# CH340G.net
KiCad netlist of a schematic drawn in Altium Designer
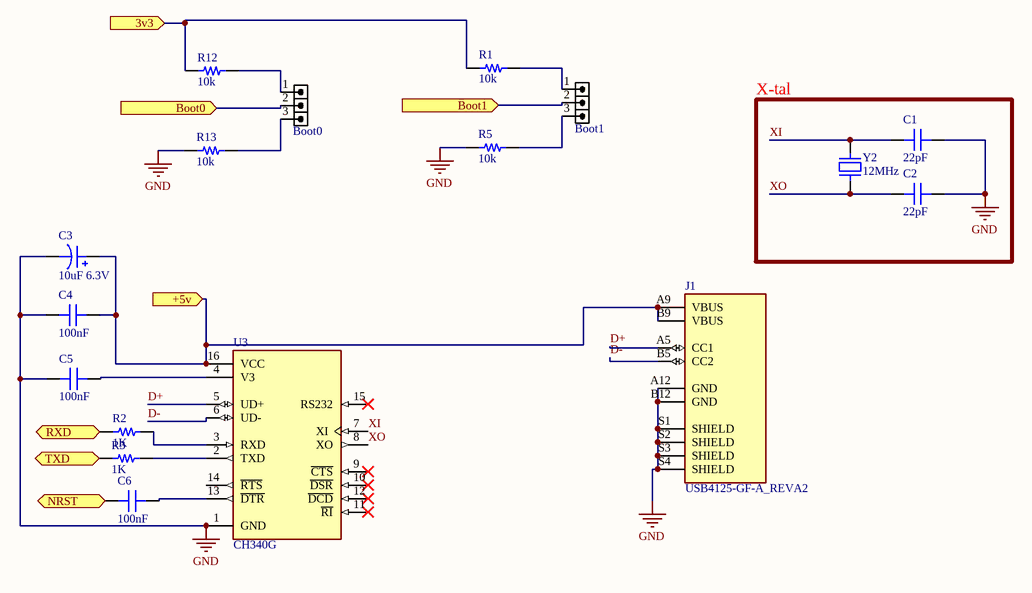
[diagram p0: CH340G.SchDoc]

(export (version "E")
  (design (tool "Eeschema 10.0.6"))
  (components
    (comp (ref "Boot0")
      (value "HDRM3")
      (footprint "HDR_1X3")
      (description "CONN, HEADER, Male, pitch: 2.54mm, 3POS")
      (libsource (lib "Conn Header") (part "HDR_1X3"))
    )
    (comp (ref "Boot1")
      (value "HDRM3")
      (footprint "HDR_1X3")
      (description "CONN, HEADER, Male, pitch: 2.54mm, 3POS")
      (libsource (lib "Conn Header") (part "HDR_1X3"))
    )
    (comp (ref "C1")
      (value "22pF")
      (footprint "CAP 0805_2012")
      (description "SMT Capacitor")
      (libsource (lib "Capacitor") (part "Cap 0805"))
    )
    (comp (ref "C2")
      (value "22pF")
      (footprint "CAP 0805_2012")
      (description "SMT Capacitor")
      (libsource (lib "Capacitor") (part "Cap 0805"))
    )
    (comp (ref "C3")
      (value "10uF 6.3V")
      (footprint "CAP ALTH D8 L3.5 H12.5")
      (description "TH Aluminum Polymer Capacitor")
      (libsource (lib "Capacitor") (part "Cap Alu TH D8mm L3.5mm H12.5mm"))
    )
    (comp (ref "C4")
      (value "100nF")
      (footprint "CAP 0805_2012")
      (description "SMT Capacitor")
      (libsource (lib "Capacitor") (part "Cap 0805"))
    )
    (comp (ref "C5")
      (value "100nF")
      (footprint "CAP 0805_2012")
      (description "SMT Capacitor")
      (libsource (lib "Capacitor") (part "Cap 0805"))
    )
    (comp (ref "C6")
      (value "100nF")
      (footprint "CAP 0805_2012")
      (description "SMT Capacitor")
      (libsource (lib "Capacitor") (part "Cap 0805"))
    )
    (comp (ref "J1")
      (value "USB4125-GF-A_REVA2")
      (footprint "GCT_USB4125-GF-A_REVA2")
      (libsource (lib "Type-C 6pin") (part "USB4125-GF-A_REVA2"))
    )
    (comp (ref "R1")
      (value "10k")
      (footprint "RES 0805_2012")
      (description "SMT Resistor")
      (libsource (lib "Resistor") (part "Res 0805"))
    )
    (comp (ref "R2")
      (value "1K")
      (footprint "RES 0805_2012")
      (description "SMT Resistor")
      (libsource (lib "Resistor") (part "Res 0805"))
    )
    (comp (ref "R3")
      (value "1K")
      (footprint "RES 0805_2012")
      (description "SMT Resistor")
      (libsource (lib "Resistor") (part "Res 0805"))
    )
    (comp (ref "R5")
      (value "10k")
      (footprint "RES 0805_2012")
      (description "SMT Resistor")
      (libsource (lib "Resistor") (part "Res 0805"))
    )
    (comp (ref "R12")
      (value "10k")
      (footprint "RES 0805_2012")
      (description "SMT Resistor")
      (libsource (lib "Resistor") (part "Res 0805"))
    )
    (comp (ref "R13")
      (value "10k")
      (footprint "RES 0805_2012")
      (description "SMT Resistor")
      (libsource (lib "Resistor") (part "Res 0805"))
    )
    (comp (ref "U3")
      (value "CH340G")
      (footprint "SOIC127P600X180-16N")
      (description "USB Interface Integrated Circuit")
      (fields (field (name "MP") "Ch340G") (field (name "MF") "WCH"))
      (libsource (lib "CH340G") (part "CH340G"))
    )
    (comp (ref "Y2")
      (value "12MHz")
      (footprint "HC-49S SMD")
      (description "SMT Crystal")
      (fields (field (name "PARTNUMBER") "ABLS-8.000MHZ-K4T"))
      (libsource (lib "Xtal") (part "Crystal HC-49S SMD 8MHz"))
    )
  )
  (nets
    (net (code "1") (name "/+5v") (class "Default")
      (node (ref "C3") (pin "1") (pinfunction "1_1") (pintype "passive"))
      (node (ref "C4") (pin "1") (pinfunction "1_1") (pintype "passive"))
      (node (ref "J1") (pin "A9") (pinfunction "VBUS_A9") (pintype "power_in"))
      (node (ref "J1") (pin "B9") (pinfunction "VBUS_B9") (pintype "power_in"))
      (node (ref "U3") (pin "16") (pinfunction "VCC_16") (pintype "power_in"))
    )
    (net (code "2") (name "/3v3") (class "Default")
      (node (ref "R1") (pin "1") (pinfunction "1_1") (pintype "passive"))
      (node (ref "R12") (pin "1") (pinfunction "1_1") (pintype "passive"))
    )
    (net (code "3") (name "/Boot0") (class "Default")
      (node (ref "Boot0") (pin "2") (pinfunction "2_2") (pintype "passive"))
    )
    (net (code "4") (name "/Boot1") (class "Default")
      (node (ref "Boot1") (pin "2") (pinfunction "2_2") (pintype "passive"))
    )
    (net (code "5") (name "/D+") (class "Default")
      (node (ref "J1") (pin "A5") (pinfunction "CC1_A5") (pintype "bidirectional"))
      (node (ref "U3") (pin "5") (pinfunction "UD+_5") (pintype "bidirectional"))
    )
    (net (code "6") (name "/D-") (class "Default")
      (node (ref "J1") (pin "B5") (pinfunction "CC2_B5") (pintype "bidirectional"))
      (node (ref "U3") (pin "6") (pinfunction "UD-_6") (pintype "bidirectional"))
    )
    (net (code "7") (name "/NRST") (class "Default")
      (node (ref "C6") (pin "1") (pinfunction "1_1") (pintype "passive"))
    )
    (net (code "8") (name "/RXD") (class "Default")
      (node (ref "R2") (pin "1") (pinfunction "1_1") (pintype "passive"))
    )
    (net (code "9") (name "/TXD") (class "Default")
      (node (ref "R3") (pin "1") (pinfunction "1_1") (pintype "passive"))
    )
    (net (code "10") (name "/XI") (class "Default")
      (node (ref "C1") (pin "1") (pinfunction "1_1") (pintype "passive"))
      (node (ref "U3") (pin "7") (pinfunction "XI_7") (pintype "input"))
      (node (ref "Y2") (pin "2") (pinfunction "2_2") (pintype "passive"))
    )
    (net (code "11") (name "/XO") (class "Default")
      (node (ref "C2") (pin "1") (pinfunction "1_1") (pintype "passive"))
      (node (ref "U3") (pin "8") (pinfunction "XO_8") (pintype "output"))
      (node (ref "Y2") (pin "1") (pinfunction "1_1") (pintype "passive"))
    )
    (net (code "12") (name "GND") (class "Default")
      (node (ref "C1") (pin "2") (pinfunction "2_2") (pintype "passive"))
      (node (ref "C2") (pin "2") (pinfunction "2_2") (pintype "passive"))
      (node (ref "C3") (pin "2") (pinfunction "2_2") (pintype "passive"))
      (node (ref "C4") (pin "2") (pinfunction "2_2") (pintype "passive"))
      (node (ref "C5") (pin "1") (pinfunction "1_1") (pintype "passive"))
      (node (ref "J1") (pin "A12") (pinfunction "GND_A12") (pintype "power_in"))
      (node (ref "J1") (pin "B12") (pinfunction "GND_B12") (pintype "power_in"))
      (node (ref "J1") (pin "S1") (pinfunction "SHIELD_S1") (pintype "passive"))
      (node (ref "J1") (pin "S2") (pinfunction "SHIELD_S2") (pintype "passive"))
      (node (ref "J1") (pin "S3") (pinfunction "SHIELD_S3") (pintype "passive"))
      (node (ref "J1") (pin "S4") (pinfunction "SHIELD_S4") (pintype "passive"))
      (node (ref "R13") (pin "1") (pinfunction "1_1") (pintype "passive"))
      (node (ref "R5") (pin "1") (pinfunction "1_1") (pintype "passive"))
      (node (ref "U3") (pin "1") (pinfunction "GND_1") (pintype "power_in"))
    )
    (net (code "13") (name "Net-(Boot0-Pad1)") (class "Default")
      (node (ref "Boot0") (pin "1") (pinfunction "1_1") (pintype "passive"))
      (node (ref "R12") (pin "2") (pinfunction "2_2") (pintype "passive"))
    )
    (net (code "14") (name "Net-(Boot0-Pad3)") (class "Default")
      (node (ref "Boot0") (pin "3") (pinfunction "3_3") (pintype "passive"))
      (node (ref "R13") (pin "2") (pinfunction "2_2") (pintype "passive"))
    )
    (net (code "15") (name "Net-(Boot1-Pad1)") (class "Default")
      (node (ref "Boot1") (pin "1") (pinfunction "1_1") (pintype "passive"))
      (node (ref "R1") (pin "2") (pinfunction "2_2") (pintype "passive"))
    )
    (net (code "16") (name "Net-(Boot1-Pad3)") (class "Default")
      (node (ref "Boot1") (pin "3") (pinfunction "3_3") (pintype "passive"))
      (node (ref "R5") (pin "2") (pinfunction "2_2") (pintype "passive"))
    )
    (net (code "17") (name "Net-(U3-RXD)") (class "Default")
      (node (ref "R2") (pin "2") (pinfunction "2_2") (pintype "passive"))
      (node (ref "U3") (pin "3") (pinfunction "RXD_3") (pintype "input"))
    )
    (net (code "18") (name "Net-(U3-TXD)") (class "Default")
      (node (ref "R3") (pin "2") (pinfunction "2_2") (pintype "passive"))
      (node (ref "U3") (pin "2") (pinfunction "TXD_2") (pintype "output"))
    )
    (net (code "19") (name "Net-(U3-V3)") (class "Default")
      (node (ref "C5") (pin "2") (pinfunction "2_2") (pintype "passive"))
      (node (ref "U3") (pin "4") (pinfunction "V3_4") (pintype "power_in"))
    )
    (net (code "20") (name "Net-(U3-~{DTR})") (class "Default")
      (node (ref "C6") (pin "2") (pinfunction "2_2") (pintype "passive"))
      (node (ref "U3") (pin "13") (pinfunction "~{DTR}_13") (pintype "output"))
    )
    (net (code "21") (name "unconnected-(U3-RS232-Pad15)") (class "Default")
      (node (ref "U3") (pin "15") (pinfunction "RS232_15") (pintype "input+no_connect"))
    )
    (net (code "22") (name "unconnected-(U3-~{CTS}-Pad9)") (class "Default")
      (node (ref "U3") (pin "9") (pinfunction "~{CTS}_9") (pintype "input+no_connect"))
    )
    (net (code "23") (name "unconnected-(U3-~{DCD}-Pad12)") (class "Default")
      (node (ref "U3") (pin "12") (pinfunction "~{DCD}_12") (pintype "input+no_connect"))
    )
    (net (code "24") (name "unconnected-(U3-~{DSR}-Pad10)") (class "Default")
      (node (ref "U3") (pin "10") (pinfunction "~{DSR}_10") (pintype "input+no_connect"))
    )
    (net (code "25") (name "unconnected-(U3-~{RI}-Pad11)") (class "Default")
      (node (ref "U3") (pin "11") (pinfunction "~{RI}_11") (pintype "input+no_connect"))
    )
    (net (code "26") (name "unconnected-(U3-~{RTS}-Pad14)") (class "Default")
      (node (ref "U3") (pin "14") (pinfunction "~{RTS}_14") (pintype "output"))
    )
  )
)
